# Bluesaab_RN52_v5_0_10pin.net
KiCad netlist of a schematic drawn in EAGLE
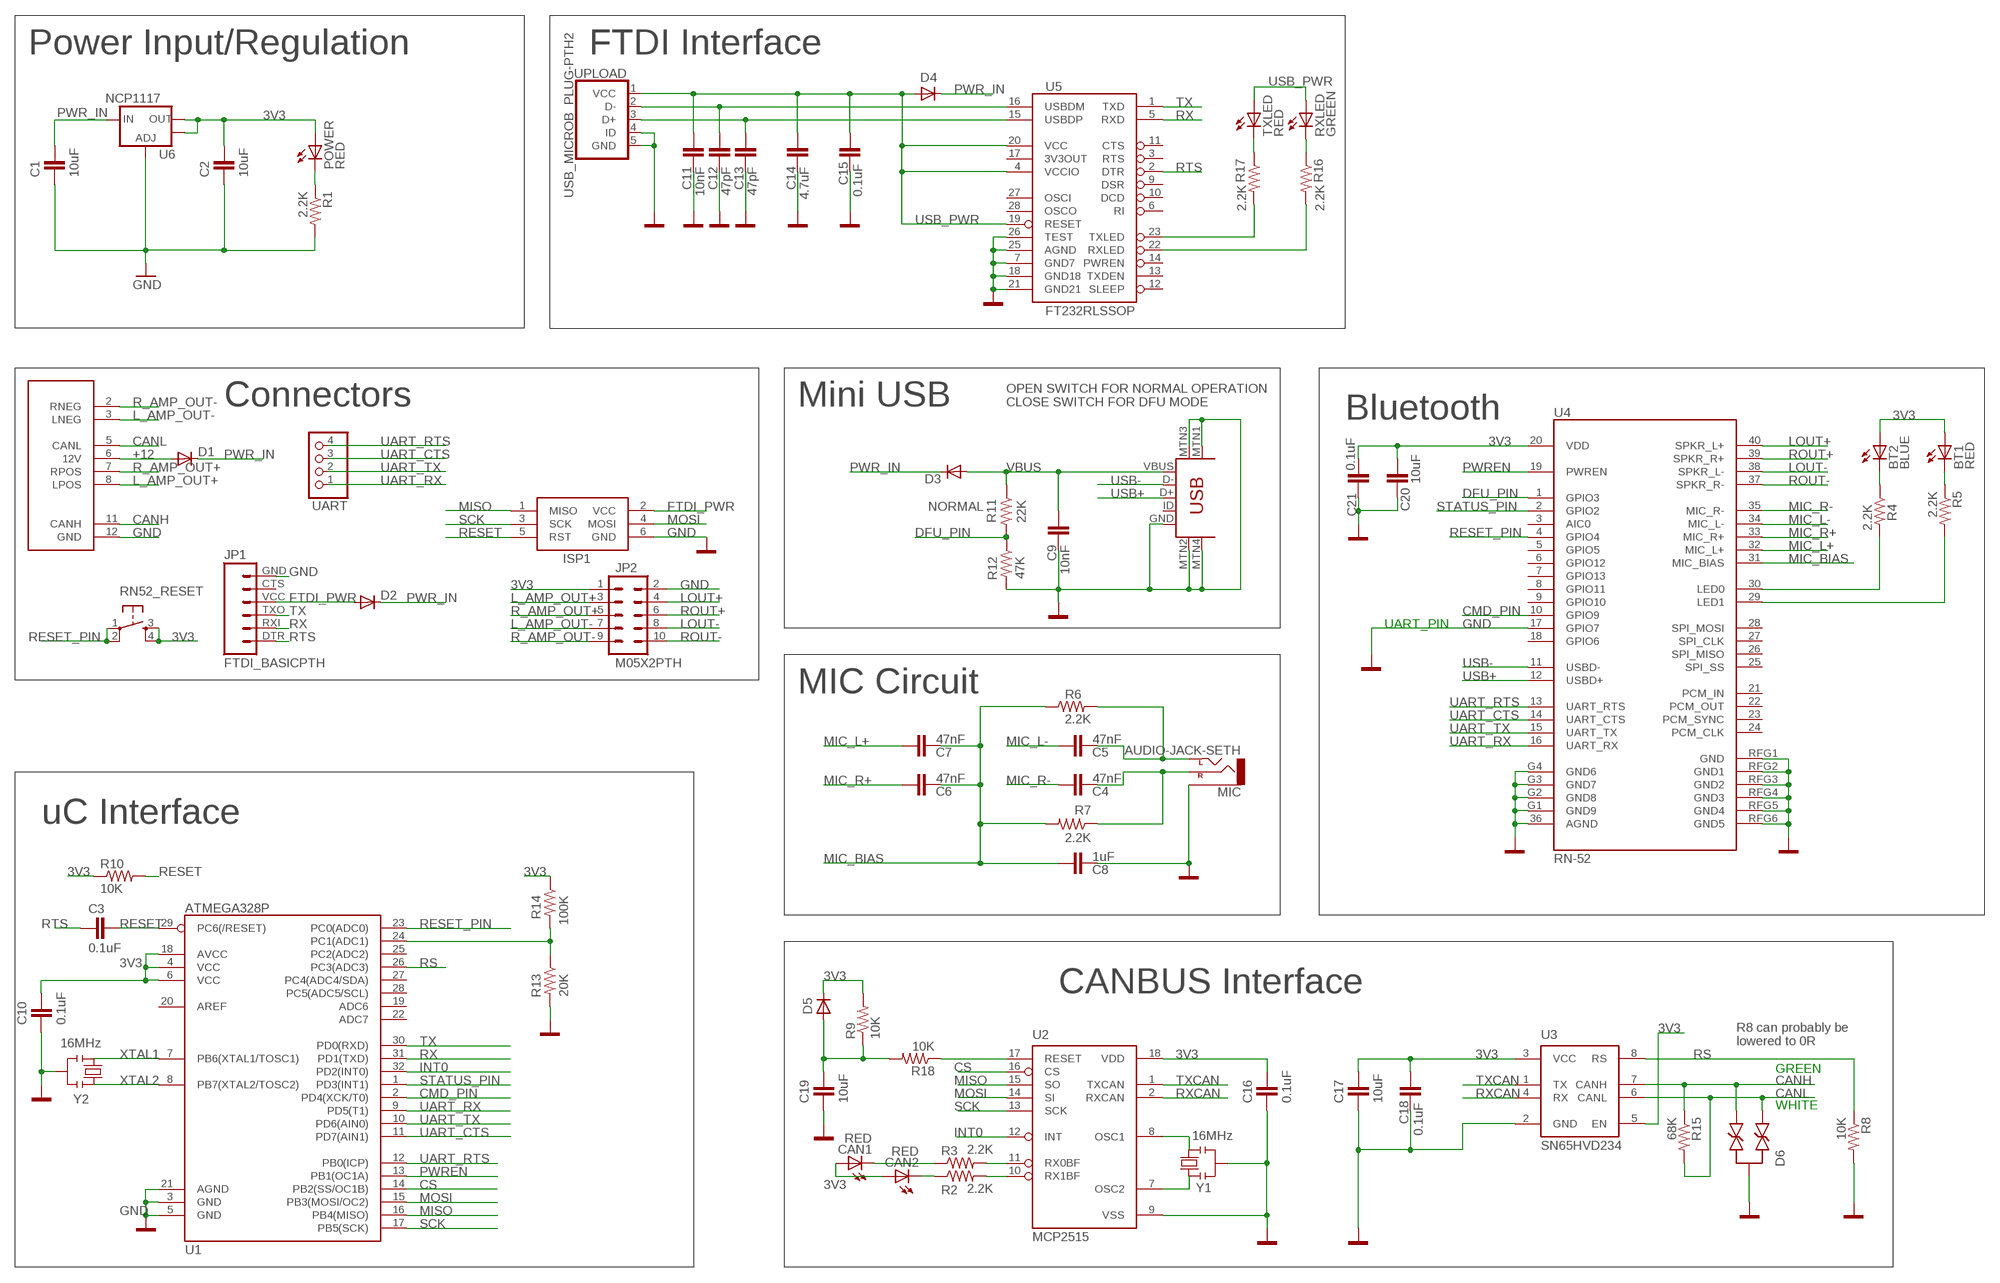
[diagram p0: schematic, sheet 1]

(export (version "E")
  (design (tool "Eeschema 10.0.6"))
  (components
    (comp (ref "BT1")
      (value "RED")
      (footprint "eagle-import:SML1206")
      (libsource (lib "eagle-import") (part "LEDSML1206"))
    )
    (comp (ref "BT2")
      (value "BLUE")
      (footprint "eagle-import:SML1206")
      (libsource (lib "eagle-import") (part "LEDSML1206"))
    )
    (comp (ref "C1")
      (value "10uF")
      (footprint "eagle-import:C0805K")
      (libsource (lib "eagle-import") (part "C-EUC0805K"))
    )
    (comp (ref "C2")
      (value "10uF")
      (footprint "eagle-import:C0805K")
      (libsource (lib "eagle-import") (part "C-EUC0805K"))
    )
    (comp (ref "C3")
      (value "0.1uF")
      (footprint "eagle-import:C0805K")
      (libsource (lib "eagle-import") (part "C-EUC0805K"))
    )
    (comp (ref "C4")
      (value "47nF")
      (footprint "eagle-import:C0805K")
      (libsource (lib "eagle-import") (part "C-EUC0805K"))
    )
    (comp (ref "C5")
      (value "47nF")
      (footprint "eagle-import:C0805K")
      (libsource (lib "eagle-import") (part "C-EUC0805K"))
    )
    (comp (ref "C6")
      (value "47nF")
      (footprint "eagle-import:C0805K")
      (libsource (lib "eagle-import") (part "C-EUC0805K"))
    )
    (comp (ref "C7")
      (value "47nF")
      (footprint "eagle-import:C0805K")
      (libsource (lib "eagle-import") (part "C-EUC0805K"))
    )
    (comp (ref "C8")
      (value "1uF")
      (footprint "eagle-import:C0805K")
      (libsource (lib "eagle-import") (part "C-EUC0805K"))
    )
    (comp (ref "C9")
      (value "10nF")
      (footprint "eagle-import:C0805K")
      (libsource (lib "eagle-import") (part "C-EUC0805K"))
    )
    (comp (ref "C10")
      (value "0.1uF")
      (footprint "eagle-import:C0805K")
      (libsource (lib "eagle-import") (part "C-EUC0805K"))
    )
    (comp (ref "C11")
      (value "10nF")
      (footprint "eagle-import:C0805K")
      (libsource (lib "eagle-import") (part "C-EUC0805K"))
    )
    (comp (ref "C12")
      (value "47pF")
      (footprint "eagle-import:C0805K")
      (libsource (lib "eagle-import") (part "C-EUC0805K"))
    )
    (comp (ref "C13")
      (value "47pF")
      (footprint "eagle-import:C0805K")
      (libsource (lib "eagle-import") (part "C-EUC0805K"))
    )
    (comp (ref "C14")
      (value "4.7uF")
      (footprint "eagle-import:C0805K")
      (libsource (lib "eagle-import") (part "C-EUC0805K"))
    )
    (comp (ref "C15")
      (value "0.1uF")
      (footprint "eagle-import:C0805K")
      (libsource (lib "eagle-import") (part "C-EUC0805K"))
    )
    (comp (ref "C16")
      (value "0.1uF")
      (footprint "eagle-import:C0805K")
      (libsource (lib "eagle-import") (part "C-EUC0805K"))
    )
    (comp (ref "C17")
      (value "10uF")
      (footprint "eagle-import:C0805K")
      (libsource (lib "eagle-import") (part "C-EUC0805K"))
    )
    (comp (ref "C18")
      (value "0.1uF")
      (footprint "eagle-import:C0805K")
      (libsource (lib "eagle-import") (part "C-EUC0805K"))
    )
    (comp (ref "C19")
      (value "10uF")
      (footprint "eagle-import:C0805K")
      (libsource (lib "eagle-import") (part "C-EUC0805K"))
    )
    (comp (ref "C20")
      (value "10uF")
      (footprint "eagle-import:C0805K")
      (libsource (lib "eagle-import") (part "C-EUC0805K"))
    )
    (comp (ref "C21")
      (value "0.1uF")
      (footprint "eagle-import:C0805K")
      (libsource (lib "eagle-import") (part "C-EUC0805K"))
    )
    (comp (ref "CAN1")
      (value "RED")
      (footprint "eagle-import:SML1206")
      (libsource (lib "eagle-import") (part "LEDSML1206"))
    )
    (comp (ref "CAN2")
      (value "RED")
      (footprint "eagle-import:SML1206")
      (libsource (lib "eagle-import") (part "LEDSML1206"))
    )
    (comp (ref "D1")
      (value "DIODE-SCHOTTKY_")
      (footprint "eagle-import:SOD123")
      (libsource (lib "eagle-import") (part "DIODE-SOD123"))
    )
    (comp (ref "D2")
      (value "DIODE-SCHOTTKY_")
      (footprint "eagle-import:SOD123")
      (libsource (lib "eagle-import") (part "DIODE-SOD123"))
    )
    (comp (ref "D3")
      (value "DIODE-SCHOTTKY_")
      (footprint "eagle-import:SOD123")
      (libsource (lib "eagle-import") (part "DIODE-SOD123"))
    )
    (comp (ref "D4")
      (value "DIODE-SCHOTTKY_")
      (footprint "eagle-import:SOD123")
      (libsource (lib "eagle-import") (part "DIODE-SOD123"))
    )
    (comp (ref "D5")
      (value "DIODE-SCHOTTKY_")
      (footprint "eagle-import:SOD123")
      (libsource (lib "eagle-import") (part "DIODE-SOD123"))
    )
    (comp (ref "D6")
      (value "DIODE-ARRAY")
      (footprint "eagle-import:SOT23")
      (libsource (lib "eagle-import") (part "DIODE-ARRAY"))
    )
    (comp (ref "ISP1")
      (value "AVRISP-6")
      (footprint "eagle-import:AVRISP")
      (libsource (lib "eagle-import") (part "AVRISP-6"))
    )
    (comp (ref "JP1")
      (value "FTDI_BASICPTH")
      (footprint "eagle-import:FTDI_BASIC")
      (libsource (lib "eagle-import") (part "FTDI_BASICPTH"))
    )
    (comp (ref "JP2")
      (value "M05X2PTH")
      (footprint "eagle-import:AVR_ICSP")
      (libsource (lib "eagle-import") (part "M05X2PTH"))
    )
    (comp (ref "MIC")
      (value "AUDIO-JACK-SETH")
      (footprint "eagle-import:AUDIO-JACK-3.5MM-SMD-SETH")
      (libsource (lib "eagle-import") (part "AUDIO-JACK-SETH"))
    )
    (comp (ref "POWER")
      (value "RED")
      (footprint "eagle-import:SML1206")
      (libsource (lib "eagle-import") (part "LEDSML1206"))
    )
    (comp (ref "R1")
      (value "2.2K")
      (footprint "eagle-import:R0805")
      (libsource (lib "eagle-import") (part "R-US_R0805"))
    )
    (comp (ref "R2")
      (value "2.2K")
      (footprint "eagle-import:R0805")
      (libsource (lib "eagle-import") (part "R-US_R0805"))
    )
    (comp (ref "R3")
      (value "2.2K")
      (footprint "eagle-import:R0805")
      (libsource (lib "eagle-import") (part "R-US_R0805"))
    )
    (comp (ref "R4")
      (value "2.2K")
      (footprint "eagle-import:R0805")
      (libsource (lib "eagle-import") (part "R-US_R0805"))
    )
    (comp (ref "R5")
      (value "2.2K")
      (footprint "eagle-import:R0805")
      (libsource (lib "eagle-import") (part "R-US_R0805"))
    )
    (comp (ref "R6")
      (value "2.2K")
      (footprint "eagle-import:R0805")
      (libsource (lib "eagle-import") (part "R-US_R0805"))
    )
    (comp (ref "R7")
      (value "2.2K")
      (footprint "eagle-import:R0805")
      (libsource (lib "eagle-import") (part "R-US_R0805"))
    )
    (comp (ref "R8")
      (value "10K")
      (footprint "eagle-import:R0805")
      (libsource (lib "eagle-import") (part "R-US_R0805"))
    )
    (comp (ref "R9")
      (value "10K")
      (footprint "eagle-import:R0805")
      (libsource (lib "eagle-import") (part "R-US_R0805"))
    )
    (comp (ref "R10")
      (value "10K")
      (footprint "eagle-import:R0805")
      (libsource (lib "eagle-import") (part "R-US_R0805"))
    )
    (comp (ref "R11")
      (value "22K")
      (footprint "eagle-import:R0805")
      (libsource (lib "eagle-import") (part "R-US_R0805"))
    )
    (comp (ref "R12")
      (value "47K")
      (footprint "eagle-import:R0805")
      (libsource (lib "eagle-import") (part "R-US_R0805"))
    )
    (comp (ref "R13")
      (value "20K")
      (footprint "eagle-import:R0805")
      (libsource (lib "eagle-import") (part "R-US_R0805"))
    )
    (comp (ref "R14")
      (value "100K")
      (footprint "eagle-import:R0805")
      (libsource (lib "eagle-import") (part "R-US_R0805"))
    )
    (comp (ref "R15")
      (value "68K")
      (footprint "eagle-import:R0805")
      (libsource (lib "eagle-import") (part "R-US_R0805"))
    )
    (comp (ref "R16")
      (value "2.2K")
      (footprint "eagle-import:R0805")
      (libsource (lib "eagle-import") (part "R-US_R0805"))
    )
    (comp (ref "R17")
      (value "2.2K")
      (footprint "eagle-import:R0805")
      (libsource (lib "eagle-import") (part "R-US_R0805"))
    )
    (comp (ref "R18")
      (value "10K")
      (footprint "eagle-import:R0805")
      (libsource (lib "eagle-import") (part "R-US_R0805"))
    )
    (comp (ref "RN52_FIRMWARE")
      (value "USB-MINIB-5PIN")
      (footprint "eagle-import:USB-MINIB")
      (libsource (lib "eagle-import") (part "USB-MINIB-5PIN"))
    )
    (comp (ref "RN52_RESET")
      (value "TAC_SWITCH")
      (footprint "eagle-import:TACTILE_SWITCH_SMD_6MM")
      (libsource (lib "eagle-import") (part "TAC_SWITCH"))
    )
    (comp (ref "RXLED")
      (value "GREEN")
      (footprint "eagle-import:SML1206")
      (libsource (lib "eagle-import") (part "LEDSML1206"))
    )
    (comp (ref "TXLED")
      (value "RED")
      (footprint "eagle-import:SML1206")
      (libsource (lib "eagle-import") (part "LEDSML1206"))
    )
    (comp (ref "U$5")
      (value "827229-1")
      (footprint "eagle-import:827229-1")
      (libsource (lib "eagle-import") (part "827229-1"))
    )
    (comp (ref "U1")
      (value "ATMEGA328P")
      (footprint "eagle-import:TQFP32-08")
      (libsource (lib "eagle-import") (part "ATMEGA328_SMT"))
    )
    (comp (ref "U2")
      (value "MCP2515")
      (footprint "eagle-import:SO18L")
      (libsource (lib "eagle-import") (part "MCP2515"))
    )
    (comp (ref "U3")
      (value "SN65HVD234")
      (footprint "eagle-import:SO8")
      (libsource (lib "eagle-import") (part "SN65HVD234"))
    )
    (comp (ref "U4")
      (value "RN-52")
      (footprint "eagle-import:RN-52")
      (libsource (lib "eagle-import") (part "BLUETOOTH-RN-52"))
    )
    (comp (ref "U5")
      (value "FT232RLSSOP")
      (footprint "eagle-import:SSOP28DB")
      (libsource (lib "eagle-import") (part "FT232RLSSOP"))
    )
    (comp (ref "U6")
      (value "NCP1117")
      (footprint "eagle-import:SOT223")
      (libsource (lib "eagle-import") (part "V_REG_LM1117SOT223"))
    )
    (comp (ref "UART")
      (value "PINHD-1X4")
      (footprint "eagle-import:1X04")
      (libsource (lib "eagle-import") (part "PINHD-1X4"))
    )
    (comp (ref "UPLOAD")
      (value "USB_MICROB_PLUG-PTH2")
      (footprint "eagle-import:MICRO-B-TH")
      (libsource (lib "eagle-import") (part "USB_MICROB_PLUG-PTH2"))
    )
    (comp (ref "Y1")
      (value "16MHz")
      (footprint "eagle-import:RESONATOR-SMD")
      (libsource (lib "eagle-import") (part "RESONATORSMD"))
    )
    (comp (ref "Y2")
      (value "16MHz")
      (footprint "eagle-import:RESONATOR-SMD")
      (libsource (lib "eagle-import") (part "RESONATORSMD"))
    )
  )
  (nets
    (net (code "1") (name "/+12") (class "Default")
      (node (ref "D1") (pin "A") (pinfunction "A_A") (pintype "passive"))
      (node (ref "U$5") (pin "6") (pinfunction "12V_6") (pintype "bidirectional"))
    )
    (net (code "2") (name "/3V3") (class "Default")
      (node (ref "BT1") (pin "A") (pinfunction "A_A") (pintype "passive"))
      (node (ref "BT2") (pin "A") (pinfunction "A_A") (pintype "passive"))
      (node (ref "C10") (pin "2") (pinfunction "2_2") (pintype "passive"))
      (node (ref "C16") (pin "2") (pinfunction "2_2") (pintype "passive"))
      (node (ref "C17") (pin "2") (pinfunction "2_2") (pintype "passive"))
      (node (ref "C18") (pin "1") (pinfunction "1_1") (pintype "passive"))
      (node (ref "C2") (pin "2") (pinfunction "2_2") (pintype "passive"))
      (node (ref "C20") (pin "1") (pinfunction "1_1") (pintype "passive"))
      (node (ref "C21") (pin "2") (pinfunction "2_2") (pintype "passive"))
      (node (ref "CAN1") (pin "A") (pinfunction "A_A") (pintype "passive"))
      (node (ref "CAN2") (pin "A") (pinfunction "A_A") (pintype "passive"))
      (node (ref "D5") (pin "C") (pinfunction "C_C") (pintype "passive"))
      (node (ref "JP2") (pin "1") (pinfunction "1_1") (pintype "passive"))
      (node (ref "POWER") (pin "A") (pinfunction "A_A") (pintype "passive"))
      (node (ref "R10") (pin "1") (pinfunction "1_1") (pintype "passive"))
      (node (ref "R14") (pin "1") (pinfunction "1_1") (pintype "passive"))
      (node (ref "R9") (pin "2") (pinfunction "2_2") (pintype "passive"))
      (node (ref "RN52_RESET") (pin "3") (pinfunction "3_3") (pintype "passive"))
      (node (ref "RN52_RESET") (pin "4") (pinfunction "4_4") (pintype "passive"))
      (node (ref "U1") (pin "18") (pinfunction "AVCC_18") (pintype "bidirectional"))
      (node (ref "U1") (pin "4") (pinfunction "VCC_4") (pintype "bidirectional"))
      (node (ref "U1") (pin "6") (pinfunction "VCC_6") (pintype "bidirectional"))
      (node (ref "U2") (pin "18") (pinfunction "VDD_18") (pintype "power_in"))
      (node (ref "U3") (pin "3") (pinfunction "VCC_3") (pintype "power_in"))
      (node (ref "U3") (pin "5") (pinfunction "EN_5") (pintype "bidirectional"))
      (node (ref "U4") (pin "20") (pinfunction "VDD_20") (pintype "bidirectional"))
      (node (ref "U6") (pin "2") (pinfunction "OUT_2") (pintype "output"))
      (node (ref "U6") (pin "4") (pinfunction "OUT_4") (pintype "output"))
    )
    (net (code "3") (name "/CANH") (class "Default")
      (node (ref "D6") (pin "2") (pinfunction "2_2") (pintype "bidirectional"))
      (node (ref "R15") (pin "1") (pinfunction "1_1") (pintype "passive"))
      (node (ref "U$5") (pin "11") (pinfunction "CANH_11") (pintype "bidirectional"))
      (node (ref "U3") (pin "7") (pinfunction "CANH_7") (pintype "bidirectional"))
    )
    (net (code "4") (name "/CANL") (class "Default")
      (node (ref "D6") (pin "1") (pinfunction "1_1") (pintype "bidirectional"))
      (node (ref "R15") (pin "2") (pinfunction "2_2") (pintype "passive"))
      (node (ref "U$5") (pin "5") (pinfunction "CANL_5") (pintype "bidirectional"))
      (node (ref "U3") (pin "6") (pinfunction "CANL_6") (pintype "bidirectional"))
    )
    (net (code "5") (name "/CMD_PIN") (class "Default")
      (node (ref "U1") (pin "2") (pinfunction "PD4(XCK/T0)_2") (pintype "bidirectional"))
      (node (ref "U4") (pin "10") (pinfunction "GPIO9_10") (pintype "bidirectional"))
    )
    (net (code "6") (name "/CS") (class "Default")
      (node (ref "U1") (pin "14") (pinfunction "PB2(SS/OC1B)_14") (pintype "bidirectional"))
      (node (ref "U2") (pin "16") (pinfunction "CS_16") (pintype "input"))
    )
    (net (code "7") (name "/DFU_PIN") (class "Default")
      (node (ref "R11") (pin "2") (pinfunction "2_2") (pintype "passive"))
      (node (ref "R12") (pin "1") (pinfunction "1_1") (pintype "passive"))
      (node (ref "U4") (pin "1") (pinfunction "GPIO3_1") (pintype "bidirectional"))
    )
    (net (code "8") (name "/FTDI_PWR") (class "Default")
      (node (ref "D2") (pin "A") (pinfunction "A_A") (pintype "passive"))
      (node (ref "ISP1") (pin "2") (pinfunction "VCC_2") (pintype "power_in"))
      (node (ref "JP1") (pin "VCC") (pinfunction "4_VCC") (pintype "passive"))
    )
    (net (code "9") (name "/INT0") (class "Default")
      (node (ref "U1") (pin "32") (pinfunction "PD2(INT0)_32") (pintype "bidirectional"))
      (node (ref "U2") (pin "12") (pinfunction "INT_12") (pintype "output"))
    )
    (net (code "10") (name "/LOUT+") (class "Default")
      (node (ref "JP2") (pin "4") (pinfunction "4_4") (pintype "passive"))
      (node (ref "U4") (pin "40") (pinfunction "SPKR_L+_40") (pintype "bidirectional"))
    )
    (net (code "11") (name "/LOUT-") (class "Default")
      (node (ref "JP2") (pin "8") (pinfunction "8_8") (pintype "passive"))
      (node (ref "U4") (pin "38") (pinfunction "SPKR_L-_38") (pintype "bidirectional"))
    )
    (net (code "12") (name "/L_AMP_OUT+") (class "Default")
      (node (ref "JP2") (pin "3") (pinfunction "3_3") (pintype "passive"))
      (node (ref "U$5") (pin "8") (pinfunction "LPOS_8") (pintype "bidirectional"))
    )
    (net (code "13") (name "/L_AMP_OUT-") (class "Default")
      (node (ref "JP2") (pin "7") (pinfunction "7_7") (pintype "passive"))
      (node (ref "U$5") (pin "3") (pinfunction "LNEG_3") (pintype "bidirectional"))
    )
    (net (code "14") (name "/MIC_BIAS") (class "Default")
      (node (ref "C6") (pin "1") (pinfunction "1_1") (pintype "passive"))
      (node (ref "C7") (pin "1") (pinfunction "1_1") (pintype "passive"))
      (node (ref "C8") (pin "2") (pinfunction "2_2") (pintype "passive"))
      (node (ref "R6") (pin "1") (pinfunction "1_1") (pintype "passive"))
      (node (ref "R7") (pin "2") (pinfunction "2_2") (pintype "passive"))
      (node (ref "U4") (pin "31") (pinfunction "MIC_BIAS_31") (pintype "bidirectional"))
    )
    (net (code "15") (name "/MIC_L+") (class "Default")
      (node (ref "C7") (pin "2") (pinfunction "2_2") (pintype "passive"))
      (node (ref "U4") (pin "32") (pinfunction "MIC_L+_32") (pintype "bidirectional"))
    )
    (net (code "16") (name "/MIC_L-") (class "Default")
      (node (ref "C5") (pin "1") (pinfunction "1_1") (pintype "passive"))
      (node (ref "U4") (pin "34") (pinfunction "MIC_L-_34") (pintype "bidirectional"))
    )
    (net (code "17") (name "/MIC_R+") (class "Default")
      (node (ref "C6") (pin "2") (pinfunction "2_2") (pintype "passive"))
      (node (ref "U4") (pin "33") (pinfunction "MIC_R+_33") (pintype "bidirectional"))
    )
    (net (code "18") (name "/MIC_R-") (class "Default")
      (node (ref "C4") (pin "1") (pinfunction "1_1") (pintype "passive"))
      (node (ref "U4") (pin "35") (pinfunction "MIC_R-_35") (pintype "bidirectional"))
    )
    (net (code "19") (name "/MISO") (class "Default")
      (node (ref "ISP1") (pin "1") (pinfunction "MISO_1") (pintype "input"))
      (node (ref "U1") (pin "16") (pinfunction "PB4(MISO)_16") (pintype "bidirectional"))
      (node (ref "U2") (pin "15") (pinfunction "SO_15") (pintype "output"))
    )
    (net (code "20") (name "/MOSI") (class "Default")
      (node (ref "ISP1") (pin "4") (pinfunction "MOSI_4") (pintype "output"))
      (node (ref "U1") (pin "15") (pinfunction "PB3(MOSI/OC2)_15") (pintype "bidirectional"))
      (node (ref "U2") (pin "14") (pinfunction "SI_14") (pintype "input"))
    )
    (net (code "21") (name "/PWREN") (class "Default")
      (node (ref "U1") (pin "13") (pinfunction "PB1(OC1A)_13") (pintype "bidirectional"))
      (node (ref "U4") (pin "19") (pinfunction "PWREN_19") (pintype "bidirectional"))
    )
    (net (code "22") (name "/PWR_IN") (class "Default")
      (node (ref "C1") (pin "2") (pinfunction "2_2") (pintype "passive"))
      (node (ref "D1") (pin "C") (pinfunction "C_C") (pintype "passive"))
      (node (ref "D2") (pin "C") (pinfunction "C_C") (pintype "passive"))
      (node (ref "D3") (pin "C") (pinfunction "C_C") (pintype "passive"))
      (node (ref "D4") (pin "C") (pinfunction "C_C") (pintype "passive"))
      (node (ref "U6") (pin "3") (pinfunction "IN_3") (pintype "input"))
    )
    (net (code "23") (name "/RESET") (class "Default")
      (node (ref "C3") (pin "2") (pinfunction "2_2") (pintype "passive"))
      (node (ref "ISP1") (pin "5") (pinfunction "RST_5") (pintype "output"))
      (node (ref "R10") (pin "2") (pinfunction "2_2") (pintype "passive"))
      (node (ref "U1") (pin "29") (pinfunction "PC6(/RESET)_29") (pintype "bidirectional"))
    )
    (net (code "24") (name "/RESET_PIN") (class "Default")
      (node (ref "RN52_RESET") (pin "1") (pinfunction "1_1") (pintype "passive"))
      (node (ref "RN52_RESET") (pin "2") (pinfunction "2_2") (pintype "passive"))
      (node (ref "U1") (pin "23") (pinfunction "PC0(ADC0)_23") (pintype "bidirectional"))
      (node (ref "U4") (pin "4") (pinfunction "GPIO4_4") (pintype "bidirectional"))
    )
    (net (code "25") (name "/ROUT+") (class "Default")
      (node (ref "JP2") (pin "6") (pinfunction "6_6") (pintype "passive"))
      (node (ref "U4") (pin "39") (pinfunction "SPKR_R+_39") (pintype "bidirectional"))
    )
    (net (code "26") (name "/ROUT-") (class "Default")
      (node (ref "JP2") (pin "10") (pinfunction "10_10") (pintype "passive"))
      (node (ref "U4") (pin "37") (pinfunction "SPKR_R-_37") (pintype "bidirectional"))
    )
    (net (code "27") (name "/RS") (class "Default")
      (node (ref "R8") (pin "1") (pinfunction "1_1") (pintype "passive"))
      (node (ref "U1") (pin "26") (pinfunction "PC3(ADC3)_26") (pintype "bidirectional"))
      (node (ref "U3") (pin "8") (pinfunction "RS_8") (pintype "bidirectional"))
    )
    (net (code "28") (name "/RTS") (class "Default")
      (node (ref "C3") (pin "1") (pinfunction "1_1") (pintype "passive"))
      (node (ref "JP1") (pin "DTR") (pinfunction "1_DTR") (pintype "passive"))
      (node (ref "U5") (pin "2") (pinfunction "DTR_2") (pintype "output"))
    )
    (net (code "29") (name "/RX") (class "Default")
      (node (ref "JP1") (pin "RXI") (pinfunction "2_RXI") (pintype "passive"))
      (node (ref "U1") (pin "31") (pinfunction "PD1(TXD)_31") (pintype "bidirectional"))
      (node (ref "U5") (pin "5") (pinfunction "RXD_5") (pintype "input"))
    )
    (net (code "30") (name "/RXCAN") (class "Default")
      (node (ref "U2") (pin "2") (pinfunction "RXCAN_2") (pintype "input"))
      (node (ref "U3") (pin "4") (pinfunction "RX_4") (pintype "output"))
    )
    (net (code "31") (name "/R_AMP_OUT+") (class "Default")
      (node (ref "JP2") (pin "5") (pinfunction "5_5") (pintype "passive"))
      (node (ref "U$5") (pin "7") (pinfunction "RPOS_7") (pintype "bidirectional"))
    )
    (net (code "32") (name "/R_AMP_OUT-") (class "Default")
      (node (ref "JP2") (pin "9") (pinfunction "9_9") (pintype "passive"))
      (node (ref "U$5") (pin "2") (pinfunction "RNEG_2") (pintype "bidirectional"))
    )
    (net (code "33") (name "/SCK") (class "Default")
      (node (ref "ISP1") (pin "3") (pinfunction "SCK_3") (pintype "output"))
      (node (ref "U1") (pin "17") (pinfunction "PB5(SCK)_17") (pintype "bidirectional"))
      (node (ref "U2") (pin "13") (pinfunction "SCK_13") (pintype "input"))
    )
    (net (code "34") (name "/STATUS_PIN") (class "Default")
      (node (ref "U1") (pin "1") (pinfunction "PD3(INT1)_1") (pintype "bidirectional"))
      (node (ref "U4") (pin "2") (pinfunction "GPIO2_2") (pintype "bidirectional"))
    )
    (net (code "35") (name "/TX") (class "Default")
      (node (ref "JP1") (pin "TXO") (pinfunction "3_TXO") (pintype "passive"))
      (node (ref "U1") (pin "30") (pinfunction "PD0(RXD)_30") (pintype "bidirectional"))
      (node (ref "U5") (pin "1") (pinfunction "TXD_1") (pintype "output"))
    )
    (net (code "36") (name "/TXCAN") (class "Default")
      (node (ref "U2") (pin "1") (pinfunction "TXCAN_1") (pintype "output"))
      (node (ref "U3") (pin "1") (pinfunction "TX_1") (pintype "input"))
    )
    (net (code "37") (name "/UART_CTS") (class "Default")
      (node (ref "U1") (pin "11") (pinfunction "PD7(AIN1)_11") (pintype "bidirectional"))
      (node (ref "U4") (pin "14") (pinfunction "UART_CTS_14") (pintype "bidirectional"))
      (node (ref "UART") (pin "3") (pinfunction "3_3") (pintype "passive"))
    )
    (net (code "38") (name "/UART_RTS") (class "Default")
      (node (ref "U1") (pin "12") (pinfunction "PB0(ICP)_12") (pintype "bidirectional"))
      (node (ref "U4") (pin "13") (pinfunction "UART_RTS_13") (pintype "bidirectional"))
      (node (ref "UART") (pin "4") (pinfunction "4_4") (pintype "passive"))
    )
    (net (code "39") (name "/UART_RX") (class "Default")
      (node (ref "U1") (pin "9") (pinfunction "PD5(T1)_9") (pintype "bidirectional"))
      (node (ref "U4") (pin "16") (pinfunction "UART_RX_16") (pintype "bidirectional"))
      (node (ref "UART") (pin "1") (pinfunction "1_1") (pintype "passive"))
    )
    (net (code "40") (name "/UART_TX") (class "Default")
      (node (ref "U1") (pin "10") (pinfunction "PD6(AIN0)_10") (pintype "bidirectional"))
      (node (ref "U4") (pin "15") (pinfunction "UART_TX_15") (pintype "bidirectional"))
      (node (ref "UART") (pin "2") (pinfunction "2_2") (pintype "passive"))
    )
    (net (code "41") (name "/USB+") (class "Default")
      (node (ref "RN52_FIRMWARE") (pin "D+") (pinfunction "D+_D+") (pintype "bidirectional"))
      (node (ref "U4") (pin "12") (pinfunction "USBD+_12") (pintype "bidirectional"))
    )
    (net (code "42") (name "/USB-") (class "Default")
      (node (ref "RN52_FIRMWARE") (pin "D-") (pinfunction "D-_D-") (pintype "bidirectional"))
      (node (ref "U4") (pin "11") (pinfunction "USBD-_11") (pintype "bidirectional"))
    )
    (net (code "43") (name "/USB_PWR") (class "Default")
      (node (ref "C11") (pin "2") (pinfunction "2_2") (pintype "passive"))
      (node (ref "C14") (pin "2") (pinfunction "2_2") (pintype "passive"))
      (node (ref "C15") (pin "1") (pinfunction "1_1") (pintype "passive"))
      (node (ref "D4") (pin "A") (pinfunction "A_A") (pintype "passive"))
      (node (ref "RXLED") (pin "A") (pinfunction "A_A") (pintype "passive"))
      (node (ref "TXLED") (pin "A") (pinfunction "A_A") (pintype "passive"))
      (node (ref "U5") (pin "19") (pinfunction "RESET_19") (pintype "input"))
      (node (ref "U5") (pin "20") (pinfunction "VCC_20") (pintype "power_in"))
      (node (ref "U5") (pin "4") (pinfunction "VCCIO_4") (pintype "power_in"))
      (node (ref "UPLOAD") (pin "1") (pinfunction "VCC_1") (pintype "bidirectional"))
    )
    (net (code "44") (name "/VBUS") (class "Default")
      (node (ref "C9") (pin "2") (pinfunction "2_2") (pintype "passive"))
      (node (ref "D3") (pin "A") (pinfunction "A_A") (pintype "passive"))
      (node (ref "R11") (pin "1") (pinfunction "1_1") (pintype "passive"))
      (node (ref "RN52_FIRMWARE") (pin "VBUS") (pinfunction "VBUS_VBUS") (pintype "bidirectional"))
    )
    (net (code "45") (name "/XTAL1") (class "Default")
      (node (ref "U1") (pin "7") (pinfunction "PB6(XTAL1/TOSC1)_7") (pintype "bidirectional"))
      (node (ref "Y2") (pin "1") (pinfunction "1_1") (pintype "bidirectional"))
    )
    (net (code "46") (name "/XTAL2") (class "Default")
      (node (ref "U1") (pin "8") (pinfunction "PB7(XTAL2/TOSC2)_8") (pintype "bidirectional"))
      (node (ref "Y2") (pin "3") (pinfunction "3_3") (pintype "bidirectional"))
    )
    (net (code "47") (name "GND") (class "Default")
      (node (ref "C1") (pin "1") (pinfunction "1_1") (pintype "passive"))
      (node (ref "C10") (pin "1") (pinfunction "1_1") (pintype "passive"))
      (node (ref "C11") (pin "1") (pinfunction "1_1") (pintype "passive"))
      (node (ref "C12") (pin "1") (pinfunction "1_1") (pintype "passive"))
      (node (ref "C13") (pin "1") (pinfunction "1_1") (pintype "passive"))
      (node (ref "C14") (pin "1") (pinfunction "1_1") (pintype "passive"))
      (node (ref "C15") (pin "2") (pinfunction "2_2") (pintype "passive"))
      (node (ref "C16") (pin "1") (pinfunction "1_1") (pintype "passive"))
      (node (ref "C17") (pin "1") (pinfunction "1_1") (pintype "passive"))
      (node (ref "C18") (pin "2") (pinfunction "2_2") (pintype "passive"))
      (node (ref "C19") (pin "1") (pinfunction "1_1") (pintype "passive"))
      (node (ref "C2") (pin "1") (pinfunction "1_1") (pintype "passive"))
      (node (ref "C20") (pin "2") (pinfunction "2_2") (pintype "passive"))
      (node (ref "C21") (pin "1") (pinfunction "1_1") (pintype "passive"))
      (node (ref "C8") (pin "1") (pinfunction "1_1") (pintype "passive"))
      (node (ref "C9") (pin "1") (pinfunction "1_1") (pintype "passive"))
      (node (ref "D6") (pin "3") (pinfunction "3_3") (pintype "bidirectional"))
      (node (ref "ISP1") (pin "6") (pinfunction "GND_6") (pintype "power_in"))
      (node (ref "JP1") (pin "GND") (pinfunction "6_GND") (pintype "passive"))
      (node (ref "JP2") (pin "2") (pinfunction "2_2") (pintype "passive"))
      (node (ref "MIC") (pin "SLEEVE") (pinfunction "SLEEVE_SLEEVE") (pintype "bidirectional"))
      (node (ref "R1") (pin "2") (pinfunction "2_2") (pintype "passive"))
      (node (ref "R12") (pin "2") (pinfunction "2_2") (pintype "passive"))
      (node (ref "R13") (pin "2") (pinfunction "2_2") (pintype "passive"))
      (node (ref "R8") (pin "2") (pinfunction "2_2") (pintype "passive"))
      (node (ref "RN52_FIRMWARE") (pin "GND") (pinfunction "GND_GND") (pintype "bidirectional"))
      (node (ref "RN52_FIRMWARE") (pin "MTN1") (pinfunction "MTN2_MTN1") (pintype "bidirectional"))
      (node (ref "RN52_FIRMWARE") (pin "MTN2") (pinfunction "MTN3_MTN2") (pintype "bidirectional"))
      (node (ref "RN52_FIRMWARE") (pin "MTN3") (pinfunction "MTN1_MTN3") (pintype "bidirectional"))
      (node (ref "RN52_FIRMWARE") (pin "MTN4") (pinfunction "MTN4_MTN4") (pintype "bidirectional"))
      (node (ref "U$5") (pin "12") (pinfunction "GND_12") (pintype "bidirectional"))
      (node (ref "U1") (pin "21") (pinfunction "AGND_21") (pintype "bidirectional"))
      (node (ref "U1") (pin "3") (pinfunction "GND_3") (pintype "bidirectional"))
      (node (ref "U1") (pin "5") (pinfunction "GND_5") (pintype "bidirectional"))
      (node (ref "U2") (pin "9") (pinfunction "VSS_9") (pintype "power_in"))
      (node (ref "U3") (pin "2") (pinfunction "GND_2") (pintype "power_in"))
      (node (ref "U4") (pin "17") (pinfunction "GPIO7_17") (pintype "bidirectional"))
      (node (ref "U4") (pin "36") (pinfunction "AGND_36") (pintype "bidirectional"))
      (node (ref "U4") (pin "G1") (pinfunction "GND9_G1") (pintype "bidirectional"))
      (node (ref "U4") (pin "G2") (pinfunction "GND8_G2") (pintype "bidirectional"))
      (node (ref "U4") (pin "G3") (pinfunction "GND7_G3") (pintype "bidirectional"))
      (node (ref "U4") (pin "G4") (pinfunction "GND6_G4") (pintype "bidirectional"))
      (node (ref "U4") (pin "RFG1") (pinfunction "GND_RFG1") (pintype "bidirectional"))
      (node (ref "U4") (pin "RFG2") (pinfunction "GND1_RFG2") (pintype "bidirectional"))
      (node (ref "U4") (pin "RFG3") (pinfunction "GND2_RFG3") (pintype "bidirectional"))
      (node (ref "U4") (pin "RFG4") (pinfunction "GND3_RFG4") (pintype "bidirectional"))
      (node (ref "U4") (pin "RFG5") (pinfunction "GND4_RFG5") (pintype "bidirectional"))
      (node (ref "U4") (pin "RFG6") (pinfunction "GND5_RFG6") (pintype "bidirectional"))
      (node (ref "U5") (pin "18") (pinfunction "GND18_18") (pintype "power_in"))
      (node (ref "U5") (pin "21") (pinfunction "GND21_21") (pintype "power_in"))
      (node (ref "U5") (pin "25") (pinfunction "AGND_25") (pintype "power_in"))
      (node (ref "U5") (pin "26") (pinfunction "TEST_26") (pintype "input"))
      (node (ref "U5") (pin "7") (pinfunction "GND7_7") (pintype "power_in"))
      (node (ref "U6") (pin "1") (pinfunction "ADJ_1") (pintype "input"))
      (node (ref "UPLOAD") (pin "4") (pinfunction "ID_4") (pintype "bidirectional"))
      (node (ref "UPLOAD") (pin "5") (pinfunction "GND_5") (pintype "bidirectional"))
      (node (ref "Y1") (pin "2") (pinfunction "2_2") (pintype "power_in"))
      (node (ref "Y2") (pin "2") (pinfunction "2_2") (pintype "power_in"))
    )
    (net (code "48") (name "Net-(BT1-PadC)") (class "Default")
      (node (ref "BT1") (pin "C") (pinfunction "C_C") (pintype "passive"))
      (node (ref "R5") (pin "1") (pinfunction "1_1") (pintype "passive"))
    )
    (net (code "49") (name "Net-(BT2-PadC)") (class "Default")
      (node (ref "BT2") (pin "C") (pinfunction "C_C") (pintype "passive"))
      (node (ref "R4") (pin "1") (pinfunction "1_1") (pintype "passive"))
    )
    (net (code "50") (name "Net-(C19-Pad2)") (class "Default")
      (node (ref "C19") (pin "2") (pinfunction "2_2") (pintype "passive"))
      (node (ref "D5") (pin "A") (pinfunction "A_A") (pintype "passive"))
      (node (ref "R18") (pin "2") (pinfunction "2_2") (pintype "passive"))
      (node (ref "R9") (pin "1") (pinfunction "1_1") (pintype "passive"))
    )
    (net (code "51") (name "Net-(CAN1-PadC)") (class "Default")
      (node (ref "CAN1") (pin "C") (pinfunction "C_C") (pintype "passive"))
      (node (ref "R3") (pin "1") (pinfunction "1_1") (pintype "passive"))
    )
    (net (code "52") (name "Net-(CAN2-PadC)") (class "Default")
      (node (ref "CAN2") (pin "C") (pinfunction "C_C") (pintype "passive"))
      (node (ref "R2") (pin "1") (pinfunction "1_1") (pintype "passive"))
    )
    (net (code "53") (name "Net-(MIC-LEFT)") (class "Default")
      (node (ref "C5") (pin "2") (pinfunction "2_2") (pintype "passive"))
      (node (ref "MIC") (pin "TIP") (pinfunction "LEFT_TIP") (pintype "bidirectional"))
      (node (ref "R6") (pin "2") (pinfunction "2_2") (pintype "passive"))
    )
    (net (code "54") (name "Net-(MIC-RIGHT)") (class "Default")
      (node (ref "C4") (pin "2") (pinfunction "2_2") (pintype "passive"))
      (node (ref "MIC") (pin "RING") (pinfunction "RIGHT_RING") (pintype "bidirectional"))
      (node (ref "R7") (pin "1") (pinfunction "1_1") (pintype "passive"))
    )
    (net (code "55") (name "Net-(POWER-PadC)") (class "Default")
      (node (ref "POWER") (pin "C") (pinfunction "C_C") (pintype "passive"))
      (node (ref "R1") (pin "1") (pinfunction "1_1") (pintype "passive"))
    )
    (net (code "56") (name "Net-(R16-Pad1)") (class "Default")
      (node (ref "R16") (pin "1") (pinfunction "1_1") (pintype "passive"))
      (node (ref "RXLED") (pin "C") (pinfunction "C_C") (pintype "passive"))
    )
    (net (code "57") (name "Net-(R17-Pad1)") (class "Default")
      (node (ref "R17") (pin "1") (pinfunction "1_1") (pintype "passive"))
      (node (ref "TXLED") (pin "C") (pinfunction "C_C") (pintype "passive"))
    )
    (net (code "58") (name "Net-(U1-PC1(ADC1))") (class "Default")
      (node (ref "R13") (pin "1") (pinfunction "1_1") (pintype "passive"))
      (node (ref "R14") (pin "2") (pinfunction "2_2") (pintype "passive"))
      (node (ref "U1") (pin "24") (pinfunction "PC1(ADC1)_24") (pintype "bidirectional"))
    )
    (net (code "59") (name "Net-(U2-OSC1)") (class "Default")
      (node (ref "U2") (pin "8") (pinfunction "OSC1_8") (pintype "input"))
      (node (ref "Y1") (pin "3") (pinfunction "3_3") (pintype "bidirectional"))
    )
    (net (code "60") (name "Net-(U2-OSC2)") (class "Default")
      (node (ref "U2") (pin "7") (pinfunction "OSC2_7") (pintype "output"))
      (node (ref "Y1") (pin "1") (pinfunction "1_1") (pintype "bidirectional"))
    )
    (net (code "61") (name "Net-(U2-RESET)") (class "Default")
      (node (ref "R18") (pin "1") (pinfunction "1_1") (pintype "passive"))
      (node (ref "U2") (pin "17") (pinfunction "RESET_17") (pintype "bidirectional"))
    )
    (net (code "62") (name "Net-(U2-RX0BF)") (class "Default")
      (node (ref "R3") (pin "2") (pinfunction "2_2") (pintype "passive"))
      (node (ref "U2") (pin "11") (pinfunction "RX0BF_11") (pintype "output"))
    )
    (net (code "63") (name "Net-(U2-RX1BF)") (class "Default")
      (node (ref "R2") (pin "2") (pinfunction "2_2") (pintype "passive"))
      (node (ref "U2") (pin "10") (pinfunction "RX1BF_10") (pintype "output"))
    )
    (net (code "64") (name "Net-(U4-LED0)") (class "Default")
      (node (ref "R4") (pin "2") (pinfunction "2_2") (pintype "passive"))
      (node (ref "U4") (pin "30") (pinfunction "LED0_30") (pintype "bidirectional"))
    )
    (net (code "65") (name "Net-(U4-LED1)") (class "Default")
      (node (ref "R5") (pin "2") (pinfunction "2_2") (pintype "passive"))
      (node (ref "U4") (pin "29") (pinfunction "LED1_29") (pintype "bidirectional"))
    )
    (net (code "66") (name "Net-(U5-RXLED)") (class "Default")
      (node (ref "R16") (pin "2") (pinfunction "2_2") (pintype "passive"))
      (node (ref "U5") (pin "22") (pinfunction "RXLED_22") (pintype "input"))
    )
    (net (code "67") (name "Net-(U5-TXLED)") (class "Default")
      (node (ref "R17") (pin "2") (pinfunction "2_2") (pintype "passive"))
      (node (ref "U5") (pin "23") (pinfunction "TXLED_23") (pintype "input"))
    )
    (net (code "68") (name "Net-(U5-USBDM)") (class "Default")
      (node (ref "C12") (pin "2") (pinfunction "2_2") (pintype "passive"))
      (node (ref "U5") (pin "16") (pinfunction "USBDM_16") (pintype "bidirectional"))
      (node (ref "UPLOAD") (pin "2") (pinfunction "D-_2") (pintype "bidirectional"))
    )
    (net (code "69") (name "Net-(U5-USBDP)") (class "Default")
      (node (ref "C13") (pin "2") (pinfunction "2_2") (pintype "passive"))
      (node (ref "U5") (pin "15") (pinfunction "USBDP_15") (pintype "bidirectional"))
      (node (ref "UPLOAD") (pin "3") (pinfunction "D+_3") (pintype "bidirectional"))
    )
    (net (code "70") (name "unconnected-(JP1-5-PadCTS)") (class "Default")
      (node (ref "JP1") (pin "CTS") (pinfunction "5_CTS") (pintype "passive"))
    )
    (net (code "71") (name "unconnected-(RN52_FIRMWARE-PadID)") (class "Default")
      (node (ref "RN52_FIRMWARE") (pin "ID") (pinfunction "ID_ID") (pintype "bidirectional"))
    )
    (net (code "72") (name "unconnected-(U1-ADC6-Pad19)") (class "Default")
      (node (ref "U1") (pin "19") (pinfunction "ADC6_19") (pintype "bidirectional"))
    )
    (net (code "73") (name "unconnected-(U1-ADC7-Pad22)") (class "Default")
      (node (ref "U1") (pin "22") (pinfunction "ADC7_22") (pintype "bidirectional"))
    )
    (net (code "74") (name "unconnected-(U1-AREF-Pad20)") (class "Default")
      (node (ref "U1") (pin "20") (pinfunction "AREF_20") (pintype "bidirectional"))
    )
    (net (code "75") (name "unconnected-(U1-PC2(ADC2)-Pad25)") (class "Default")
      (node (ref "U1") (pin "25") (pinfunction "PC2(ADC2)_25") (pintype "bidirectional"))
    )
    (net (code "76") (name "unconnected-(U1-PC4(ADC4{slash}SDA)-Pad27)") (class "Default")
      (node (ref "U1") (pin "27") (pinfunction "PC4(ADC4/SDA)_27") (pintype "bidirectional"))
    )
    (net (code "77") (name "unconnected-(U1-PC5(ADC5{slash}SCL)-Pad28)") (class "Default")
      (node (ref "U1") (pin "28") (pinfunction "PC5(ADC5/SCL)_28") (pintype "bidirectional"))
    )
    (net (code "78") (name "unconnected-(U4-AIC0-Pad3)") (class "Default")
      (node (ref "U4") (pin "3") (pinfunction "AIC0_3") (pintype "bidirectional"))
    )
    (net (code "79") (name "unconnected-(U4-GPIO5-Pad5)") (class "Default")
      (node (ref "U4") (pin "5") (pinfunction "GPIO5_5") (pintype "bidirectional"))
    )
    (net (code "80") (name "unconnected-(U4-GPIO6-Pad18)") (class "Default")
      (node (ref "U4") (pin "18") (pinfunction "GPIO6_18") (pintype "bidirectional"))
    )
    (net (code "81") (name "unconnected-(U4-GPIO10-Pad9)") (class "Default")
      (node (ref "U4") (pin "9") (pinfunction "GPIO10_9") (pintype "bidirectional"))
    )
    (net (code "82") (name "unconnected-(U4-GPIO11-Pad8)") (class "Default")
      (node (ref "U4") (pin "8") (pinfunction "GPIO11_8") (pintype "bidirectional"))
    )
    (net (code "83") (name "unconnected-(U4-GPIO12-Pad6)") (class "Default")
      (node (ref "U4") (pin "6") (pinfunction "GPIO12_6") (pintype "bidirectional"))
    )
    (net (code "84") (name "unconnected-(U4-GPIO13-Pad7)") (class "Default")
      (node (ref "U4") (pin "7") (pinfunction "GPIO13_7") (pintype "bidirectional"))
    )
    (net (code "85") (name "unconnected-(U4-PCM_CLK-Pad24)") (class "Default")
      (node (ref "U4") (pin "24") (pinfunction "PCM_CLK_24") (pintype "bidirectional"))
    )
    (net (code "86") (name "unconnected-(U4-PCM_IN-Pad21)") (class "Default")
      (node (ref "U4") (pin "21") (pinfunction "PCM_IN_21") (pintype "bidirectional"))
    )
    (net (code "87") (name "unconnected-(U4-PCM_OUT-Pad22)") (class "Default")
      (node (ref "U4") (pin "22") (pinfunction "PCM_OUT_22") (pintype "bidirectional"))
    )
    (net (code "88") (name "unconnected-(U4-PCM_SYNC-Pad23)") (class "Default")
      (node (ref "U4") (pin "23") (pinfunction "PCM_SYNC_23") (pintype "bidirectional"))
    )
    (net (code "89") (name "unconnected-(U4-SPI_CLK-Pad27)") (class "Default")
      (node (ref "U4") (pin "27") (pinfunction "SPI_CLK_27") (pintype "bidirectional"))
    )
    (net (code "90") (name "unconnected-(U4-SPI_MISO-Pad26)") (class "Default")
      (node (ref "U4") (pin "26") (pinfunction "SPI_MISO_26") (pintype "bidirectional"))
    )
    (net (code "91") (name "unconnected-(U4-SPI_MOSI-Pad28)") (class "Default")
      (node (ref "U4") (pin "28") (pinfunction "SPI_MOSI_28") (pintype "bidirectional"))
    )
    (net (code "92") (name "unconnected-(U4-SPI_SS-Pad25)") (class "Default")
      (node (ref "U4") (pin "25") (pinfunction "SPI_SS_25") (pintype "bidirectional"))
    )
    (net (code "93") (name "unconnected-(U5-3V3OUT-Pad17)") (class "Default")
      (node (ref "U5") (pin "17") (pinfunction "3V3OUT_17") (pintype "output"))
    )
    (net (code "94") (name "unconnected-(U5-CTS-Pad11)") (class "Default")
      (node (ref "U5") (pin "11") (pinfunction "CTS_11") (pintype "input"))
    )
    (net (code "95") (name "unconnected-(U5-DCD-Pad10)") (class "Default")
      (node (ref "U5") (pin "10") (pinfunction "DCD_10") (pintype "input"))
    )
    (net (code "96") (name "unconnected-(U5-DSR-Pad9)") (class "Default")
      (node (ref "U5") (pin "9") (pinfunction "DSR_9") (pintype "input"))
    )
    (net (code "97") (name "unconnected-(U5-OSCI-Pad27)") (class "Default")
      (node (ref "U5") (pin "27") (pinfunction "OSCI_27") (pintype "input"))
    )
    (net (code "98") (name "unconnected-(U5-OSCO-Pad28)") (class "Default")
      (node (ref "U5") (pin "28") (pinfunction "OSCO_28") (pintype "output"))
    )
    (net (code "99") (name "unconnected-(U5-PWREN-Pad14)") (class "Default")
      (node (ref "U5") (pin "14") (pinfunction "PWREN_14") (pintype "input"))
    )
    (net (code "100") (name "unconnected-(U5-RI-Pad6)") (class "Default")
      (node (ref "U5") (pin "6") (pinfunction "RI_6") (pintype "input"))
    )
    (net (code "101") (name "unconnected-(U5-RTS-Pad3)") (class "Default")
      (node (ref "U5") (pin "3") (pinfunction "RTS_3") (pintype "output"))
    )
    (net (code "102") (name "unconnected-(U5-SLEEP-Pad12)") (class "Default")
      (node (ref "U5") (pin "12") (pinfunction "SLEEP_12") (pintype "input"))
    )
    (net (code "103") (name "unconnected-(U5-TXDEN-Pad13)") (class "Default")
      (node (ref "U5") (pin "13") (pinfunction "TXDEN_13") (pintype "input"))
    )
  )
)
